# MSP430-Reaction-Game-Modified.net
KiCad netlist of a schematic drawn in EAGLE
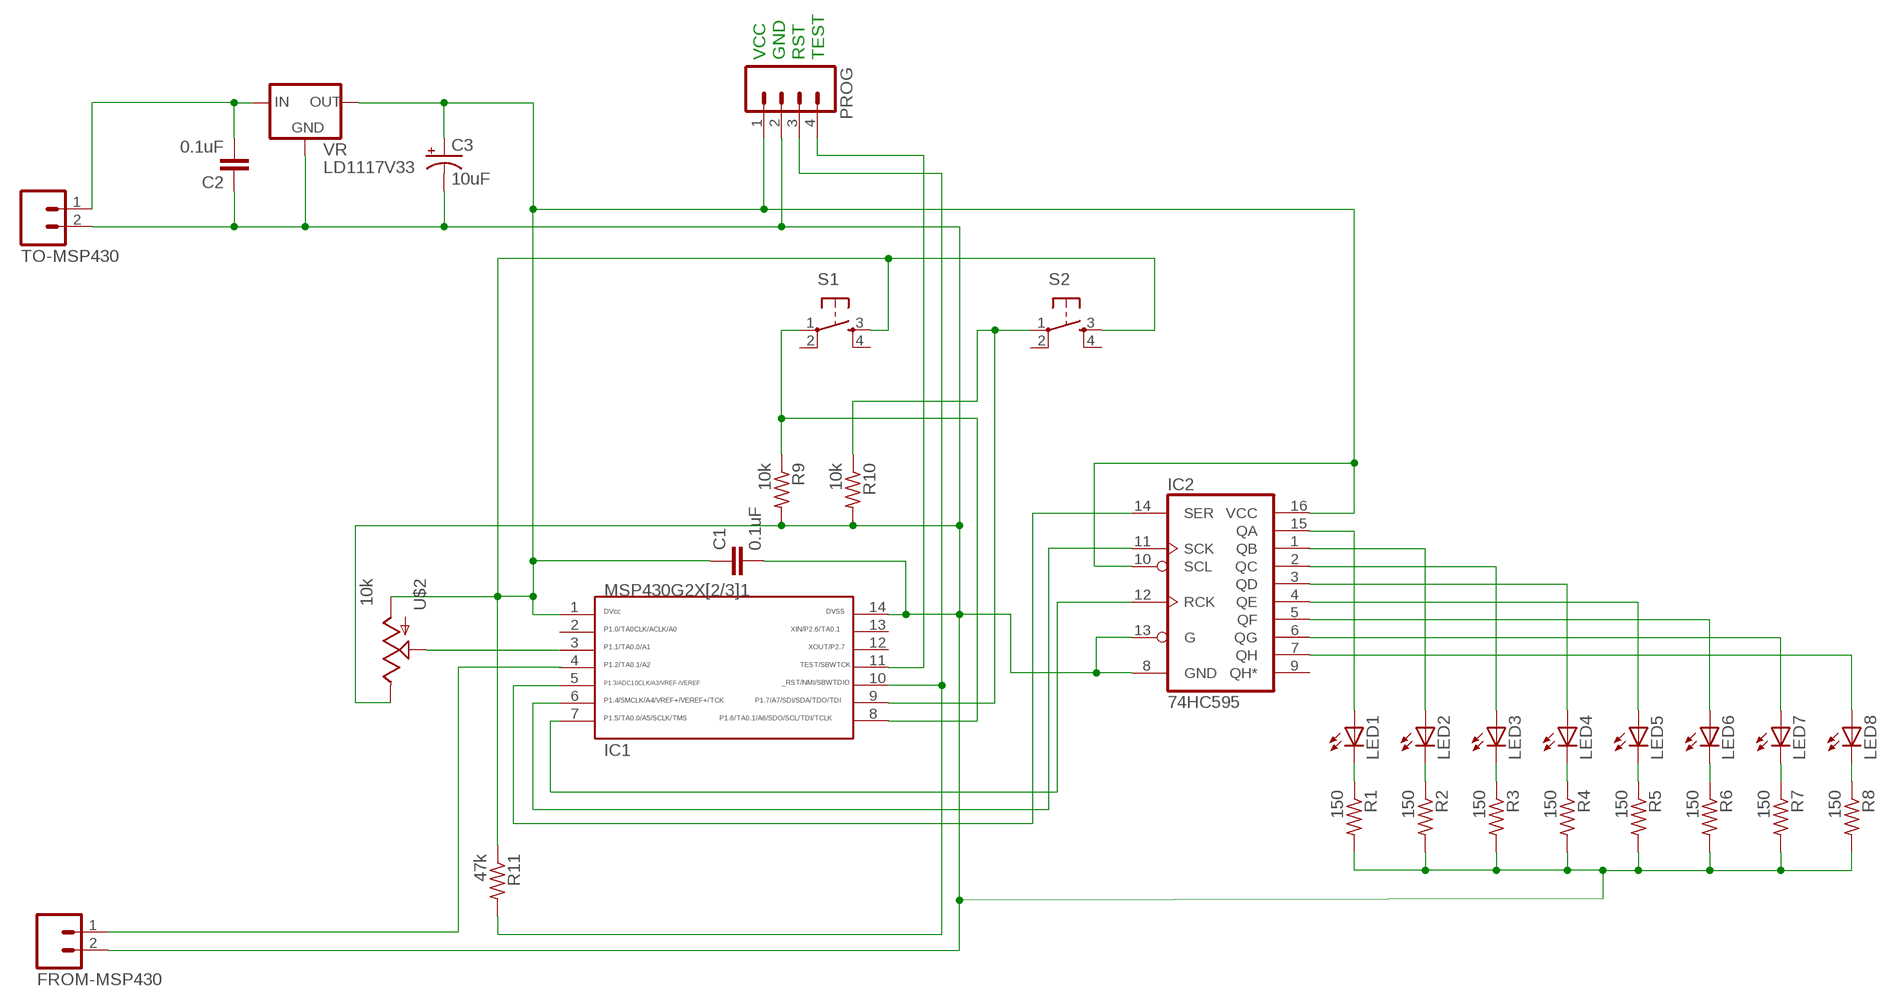
[diagram p0: schematic, sheet 1]

(export (version "E")
  (design (tool "Eeschema 10.0.6"))
  (components
    (comp (ref "C1")
      (value "0.1uF")
      (footprint "eagle-import:CAP-PTH-SMALL2")
      (libsource (lib "eagle-import") (part "CAPPTH2"))
    )
    (comp (ref "C2")
      (value "0.1uF")
      (footprint "eagle-import:CAP-PTH-SMALL2")
      (libsource (lib "eagle-import") (part "CAPPTH2"))
    )
    (comp (ref "C3")
      (value "10uF")
      (footprint "eagle-import:CPOL-RADIAL-100UF-25V")
      (libsource (lib "eagle-import") (part "CAP_POLPTH1"))
    )
    (comp (ref "FROM-MSP430")
      (value "M02PTH3")
      (footprint "eagle-import:1X02_LONGPADS")
      (libsource (lib "eagle-import") (part "M02PTH3"))
    )
    (comp (ref "IC1")
      (value "MSP430G2231")
      (footprint "eagle-import:N14")
      (libsource (lib "eagle-import") (part "G2X[2/3]1---N14"))
    )
    (comp (ref "IC2")
      (value "74HC595")
      (footprint "eagle-import:DIL16")
      (libsource (lib "eagle-import") (part "74595NLS"))
    )
    (comp (ref "LED1")
      (value "LED5MM")
      (footprint "eagle-import:LED5MM")
      (libsource (lib "eagle-import") (part "LED5MM"))
    )
    (comp (ref "LED2")
      (value "LED5MM")
      (footprint "eagle-import:LED5MM")
      (libsource (lib "eagle-import") (part "LED5MM"))
    )
    (comp (ref "LED3")
      (value "LED5MM")
      (footprint "eagle-import:LED5MM")
      (libsource (lib "eagle-import") (part "LED5MM"))
    )
    (comp (ref "LED4")
      (value "LED5MM")
      (footprint "eagle-import:LED5MM")
      (libsource (lib "eagle-import") (part "LED5MM"))
    )
    (comp (ref "LED5")
      (value "LED5MM")
      (footprint "eagle-import:LED5MM")
      (libsource (lib "eagle-import") (part "LED5MM"))
    )
    (comp (ref "LED6")
      (value "LED5MM")
      (footprint "eagle-import:LED5MM")
      (libsource (lib "eagle-import") (part "LED5MM"))
    )
    (comp (ref "LED7")
      (value "LED5MM")
      (footprint "eagle-import:LED5MM")
      (libsource (lib "eagle-import") (part "LED5MM"))
    )
    (comp (ref "LED8")
      (value "LED5MM")
      (footprint "eagle-import:LED5MM")
      (libsource (lib "eagle-import") (part "LED5MM"))
    )
    (comp (ref "PROG")
      (value "M04LOCK")
      (footprint "eagle-import:1X04_LOCK")
      (libsource (lib "eagle-import") (part "M04LOCK"))
    )
    (comp (ref "R1")
      (value "150")
      (footprint "eagle-import:0207_10")
      (libsource (lib "eagle-import") (part "R-US_0207/10"))
    )
    (comp (ref "R2")
      (value "150")
      (footprint "eagle-import:0207_10")
      (libsource (lib "eagle-import") (part "R-US_0207/10"))
    )
    (comp (ref "R3")
      (value "150")
      (footprint "eagle-import:0207_10")
      (libsource (lib "eagle-import") (part "R-US_0207/10"))
    )
    (comp (ref "R4")
      (value "150")
      (footprint "eagle-import:0207_10")
      (libsource (lib "eagle-import") (part "R-US_0207/10"))
    )
    (comp (ref "R5")
      (value "150")
      (footprint "eagle-import:0207_10")
      (libsource (lib "eagle-import") (part "R-US_0207/10"))
    )
    (comp (ref "R6")
      (value "150")
      (footprint "eagle-import:0207_10")
      (libsource (lib "eagle-import") (part "R-US_0207/10"))
    )
    (comp (ref "R7")
      (value "150")
      (footprint "eagle-import:0207_10")
      (libsource (lib "eagle-import") (part "R-US_0207/10"))
    )
    (comp (ref "R8")
      (value "150")
      (footprint "eagle-import:0207_10")
      (libsource (lib "eagle-import") (part "R-US_0207/10"))
    )
    (comp (ref "R9")
      (value "10k")
      (footprint "eagle-import:0207_10")
      (libsource (lib "eagle-import") (part "R-US_0207/10"))
    )
    (comp (ref "R10")
      (value "10k")
      (footprint "eagle-import:0207_10")
      (libsource (lib "eagle-import") (part "R-US_0207/10"))
    )
    (comp (ref "R11")
      (value "47k")
      (footprint "eagle-import:0207_10")
      (libsource (lib "eagle-import") (part "R-US_0207/10"))
    )
    (comp (ref "S1")
      (value "TAC_SWITCHPTH")
      (footprint "eagle-import:TACTILE-PTH")
      (libsource (lib "eagle-import") (part "TAC_SWITCHPTH"))
    )
    (comp (ref "S2")
      (value "TAC_SWITCHPTH")
      (footprint "eagle-import:TACTILE-PTH")
      (libsource (lib "eagle-import") (part "TAC_SWITCHPTH"))
    )
    (comp (ref "TO-MSP430")
      (value "M02PTH3")
      (footprint "eagle-import:1X02_LONGPADS")
      (libsource (lib "eagle-import") (part "M02PTH3"))
    )
    (comp (ref "U$2")
      (value "10k")
      (footprint "eagle-import:ALPS_POT")
      (libsource (lib "eagle-import") (part "POT"))
    )
    (comp (ref "VR")
      (value "LD1117V33")
      (footprint "eagle-import:78XXL")
      (libsource (lib "eagle-import") (part "V_REG_LD1117VXX"))
    )
  )
  (nets
    (net (code "1") (name "Net-(C3-+)") (class "Default")
      (node (ref "C1") (pin "1") (pinfunction "1_1") (pintype "passive"))
      (node (ref "C3") (pin "1") (pinfunction "+_1") (pintype "passive"))
      (node (ref "IC1") (pin "1") (pinfunction "1_1") (pintype "bidirectional"))
      (node (ref "IC2") (pin "10") (pinfunction "SCL_10") (pintype "input"))
      (node (ref "IC2") (pin "16") (pinfunction "VCC_16") (pintype "power_in"))
      (node (ref "PROG") (pin "1") (pinfunction "1_1") (pintype "passive"))
      (node (ref "R11") (pin "1") (pinfunction "1_1") (pintype "passive"))
      (node (ref "S1") (pin "3") (pinfunction "3_3") (pintype "passive"))
      (node (ref "S2") (pin "3") (pinfunction "3_3") (pintype "passive"))
      (node (ref "U$2") (pin "P$3") (pinfunction "A_P$3") (pintype "passive"))
      (node (ref "VR") (pin "GND") (pinfunction "OUT_GND") (pintype "output"))
    )
    (net (code "2") (name "Net-(C3--)") (class "Default")
      (node (ref "C1") (pin "2") (pinfunction "2_2") (pintype "passive"))
      (node (ref "C2") (pin "1") (pinfunction "1_1") (pintype "passive"))
      (node (ref "C3") (pin "2") (pinfunction "-_2") (pintype "passive"))
      (node (ref "FROM-MSP430") (pin "2") (pinfunction "2_2") (pintype "passive"))
      (node (ref "IC1") (pin "14") (pinfunction "14_14") (pintype "bidirectional"))
      (node (ref "IC2") (pin "13") (pinfunction "G_13") (pintype "input"))
      (node (ref "IC2") (pin "8") (pinfunction "GND_8") (pintype "power_in"))
      (node (ref "PROG") (pin "2") (pinfunction "2_2") (pintype "passive"))
      (node (ref "R1") (pin "2") (pinfunction "2_2") (pintype "passive"))
      (node (ref "R10") (pin "2") (pinfunction "2_2") (pintype "passive"))
      (node (ref "R2") (pin "2") (pinfunction "2_2") (pintype "passive"))
      (node (ref "R3") (pin "2") (pinfunction "2_2") (pintype "passive"))
      (node (ref "R4") (pin "2") (pinfunction "2_2") (pintype "passive"))
      (node (ref "R5") (pin "2") (pinfunction "2_2") (pintype "passive"))
      (node (ref "R6") (pin "2") (pinfunction "2_2") (pintype "passive"))
      (node (ref "R7") (pin "2") (pinfunction "2_2") (pintype "passive"))
      (node (ref "R8") (pin "2") (pinfunction "2_2") (pintype "passive"))
      (node (ref "R9") (pin "2") (pinfunction "2_2") (pintype "passive"))
      (node (ref "TO-MSP430") (pin "2") (pinfunction "2_2") (pintype "passive"))
      (node (ref "U$2") (pin "P$1") (pinfunction "E_P$1") (pintype "passive"))
      (node (ref "VR") (pin "IN") (pinfunction "GND_IN") (pintype "input"))
    )
    (net (code "3") (name "Net-(IC1-Pad8)") (class "Default")
      (node (ref "IC1") (pin "8") (pinfunction "8_8") (pintype "bidirectional"))
      (node (ref "R9") (pin "1") (pinfunction "1_1") (pintype "passive"))
      (node (ref "S1") (pin "1") (pinfunction "1_1") (pintype "passive"))
    )
    (net (code "4") (name "Net-(IC1-Pad9)") (class "Default")
      (node (ref "IC1") (pin "9") (pinfunction "9_9") (pintype "bidirectional"))
      (node (ref "R10") (pin "1") (pinfunction "1_1") (pintype "passive"))
      (node (ref "S2") (pin "1") (pinfunction "1_1") (pintype "passive"))
    )
    (net (code "5") (name "Net-(IC1-Pad10)") (class "Default")
      (node (ref "IC1") (pin "10") (pinfunction "10_10") (pintype "bidirectional"))
      (node (ref "PROG") (pin "3") (pinfunction "3_3") (pintype "passive"))
      (node (ref "R11") (pin "2") (pinfunction "2_2") (pintype "passive"))
    )
    (net (code "6") (name "Net-(IC1-Pad11)") (class "Default")
      (node (ref "IC1") (pin "11") (pinfunction "11_11") (pintype "bidirectional"))
      (node (ref "PROG") (pin "4") (pinfunction "4_4") (pintype "passive"))
    )
    (net (code "7") (name "Net-(IC2-QA)") (class "Default")
      (node (ref "IC2") (pin "15") (pinfunction "QA_15") (pintype "tri_state"))
      (node (ref "LED1") (pin "A") (pinfunction "A_A") (pintype "passive"))
    )
    (net (code "8") (name "Net-(IC2-QB)") (class "Default")
      (node (ref "IC2") (pin "1") (pinfunction "QB_1") (pintype "tri_state"))
      (node (ref "LED2") (pin "A") (pinfunction "A_A") (pintype "passive"))
    )
    (net (code "9") (name "Net-(IC2-QC)") (class "Default")
      (node (ref "IC2") (pin "2") (pinfunction "QC_2") (pintype "tri_state"))
      (node (ref "LED3") (pin "A") (pinfunction "A_A") (pintype "passive"))
    )
    (net (code "10") (name "Net-(IC2-QD)") (class "Default")
      (node (ref "IC2") (pin "3") (pinfunction "QD_3") (pintype "tri_state"))
      (node (ref "LED4") (pin "A") (pinfunction "A_A") (pintype "passive"))
    )
    (net (code "11") (name "Net-(IC2-QE)") (class "Default")
      (node (ref "IC2") (pin "4") (pinfunction "QE_4") (pintype "tri_state"))
      (node (ref "LED5") (pin "A") (pinfunction "A_A") (pintype "passive"))
    )
    (net (code "12") (name "Net-(IC2-QF)") (class "Default")
      (node (ref "IC2") (pin "5") (pinfunction "QF_5") (pintype "tri_state"))
      (node (ref "LED6") (pin "A") (pinfunction "A_A") (pintype "passive"))
    )
    (net (code "13") (name "Net-(IC2-QG)") (class "Default")
      (node (ref "IC2") (pin "6") (pinfunction "QG_6") (pintype "tri_state"))
      (node (ref "LED7") (pin "A") (pinfunction "A_A") (pintype "passive"))
    )
    (net (code "14") (name "Net-(IC2-QH)") (class "Default")
      (node (ref "IC2") (pin "7") (pinfunction "QH_7") (pintype "tri_state"))
      (node (ref "LED8") (pin "A") (pinfunction "A_A") (pintype "passive"))
    )
    (net (code "15") (name "Net-(IC2-RCK)") (class "Default")
      (node (ref "IC1") (pin "7") (pinfunction "7_7") (pintype "bidirectional"))
      (node (ref "IC2") (pin "12") (pinfunction "RCK_12") (pintype "input"))
    )
    (net (code "16") (name "Net-(IC2-SCK)") (class "Default")
      (node (ref "IC1") (pin "6") (pinfunction "6_6") (pintype "bidirectional"))
      (node (ref "IC2") (pin "11") (pinfunction "SCK_11") (pintype "input"))
    )
    (net (code "17") (name "Net-(IC2-SER)") (class "Default")
      (node (ref "IC1") (pin "5") (pinfunction "5_5") (pintype "bidirectional"))
      (node (ref "IC2") (pin "14") (pinfunction "SER_14") (pintype "input"))
    )
    (net (code "18") (name "Net-(LED1-C)") (class "Default")
      (node (ref "LED1") (pin "K") (pinfunction "C_K") (pintype "passive"))
      (node (ref "R1") (pin "1") (pinfunction "1_1") (pintype "passive"))
    )
    (net (code "19") (name "Net-(LED2-C)") (class "Default")
      (node (ref "LED2") (pin "K") (pinfunction "C_K") (pintype "passive"))
      (node (ref "R2") (pin "1") (pinfunction "1_1") (pintype "passive"))
    )
    (net (code "20") (name "Net-(LED3-C)") (class "Default")
      (node (ref "LED3") (pin "K") (pinfunction "C_K") (pintype "passive"))
      (node (ref "R3") (pin "1") (pinfunction "1_1") (pintype "passive"))
    )
    (net (code "21") (name "Net-(LED4-C)") (class "Default")
      (node (ref "LED4") (pin "K") (pinfunction "C_K") (pintype "passive"))
      (node (ref "R4") (pin "1") (pinfunction "1_1") (pintype "passive"))
    )
    (net (code "22") (name "Net-(LED5-C)") (class "Default")
      (node (ref "LED5") (pin "K") (pinfunction "C_K") (pintype "passive"))
      (node (ref "R5") (pin "1") (pinfunction "1_1") (pintype "passive"))
    )
    (net (code "23") (name "Net-(LED6-C)") (class "Default")
      (node (ref "LED6") (pin "K") (pinfunction "C_K") (pintype "passive"))
      (node (ref "R6") (pin "1") (pinfunction "1_1") (pintype "passive"))
    )
    (net (code "24") (name "Net-(LED7-C)") (class "Default")
      (node (ref "LED7") (pin "K") (pinfunction "C_K") (pintype "passive"))
      (node (ref "R7") (pin "1") (pinfunction "1_1") (pintype "passive"))
    )
    (net (code "25") (name "Net-(LED8-C)") (class "Default")
      (node (ref "LED8") (pin "K") (pinfunction "C_K") (pintype "passive"))
      (node (ref "R8") (pin "1") (pinfunction "1_1") (pintype "passive"))
    )
    (net (code "26") (name "Net-(U$2-S)") (class "Default")
      (node (ref "IC1") (pin "3") (pinfunction "3_3") (pintype "bidirectional"))
      (node (ref "U$2") (pin "P$2") (pinfunction "S_P$2") (pintype "passive"))
    )
    (net (code "27") (name "Net-(VR-IN)") (class "Default")
      (node (ref "C2") (pin "2") (pinfunction "2_2") (pintype "passive"))
      (node (ref "TO-MSP430") (pin "1") (pinfunction "1_1") (pintype "passive"))
      (node (ref "VR") (pin "OUT") (pinfunction "IN_OUT") (pintype "input"))
    )
    (net (code "28") (name "unconnected-(FROM-MSP430-Pad1)") (class "Default")
      (node (ref "FROM-MSP430") (pin "1") (pinfunction "1_1") (pintype "passive"))
    )
    (net (code "29") (name "unconnected-(IC1-Pad2)") (class "Default")
      (node (ref "IC1") (pin "2") (pinfunction "2_2") (pintype "bidirectional"))
    )
    (net (code "30") (name "unconnected-(IC1-Pad4)") (class "Default")
      (node (ref "IC1") (pin "4") (pinfunction "4_4") (pintype "bidirectional"))
    )
    (net (code "31") (name "unconnected-(IC1-Pad12)") (class "Default")
      (node (ref "IC1") (pin "12") (pinfunction "12_12") (pintype "bidirectional"))
    )
    (net (code "32") (name "unconnected-(IC1-Pad13)") (class "Default")
      (node (ref "IC1") (pin "13") (pinfunction "13_13") (pintype "bidirectional"))
    )
    (net (code "33") (name "unconnected-(IC2-QH*-Pad9)") (class "Default")
      (node (ref "IC2") (pin "9") (pinfunction "QH*_9") (pintype "tri_state"))
    )
    (net (code "34") (name "unconnected-(S1-Pad2)") (class "Default")
      (node (ref "S1") (pin "2") (pinfunction "2_2") (pintype "passive"))
    )
    (net (code "35") (name "unconnected-(S1-Pad4)") (class "Default")
      (node (ref "S1") (pin "4") (pinfunction "4_4") (pintype "passive"))
    )
    (net (code "36") (name "unconnected-(S2-Pad2)") (class "Default")
      (node (ref "S2") (pin "2") (pinfunction "2_2") (pintype "passive"))
    )
    (net (code "37") (name "unconnected-(S2-Pad4)") (class "Default")
      (node (ref "S2") (pin "4") (pinfunction "4_4") (pintype "passive"))
    )
  )
)
